# CAN.net
KiCad netlist of a schematic drawn in Altium Designer
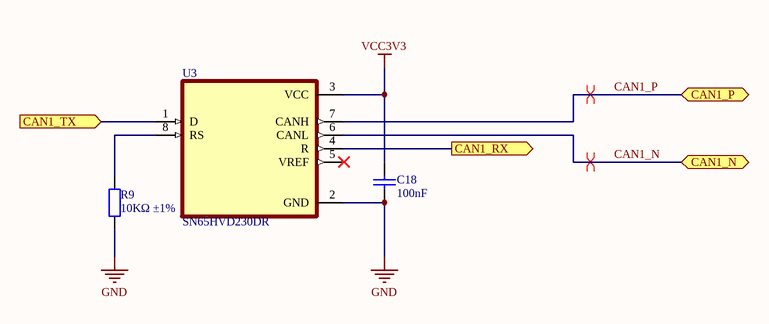
[diagram p0: CAN.SchDoc]

(export (version "E")
  (design (tool "Eeschema 10.0.6"))
  (components
    (comp (ref "C18")
      (value "100nF")
      (footprint "0402_C")
      (description "Chip capacitors")
      (fields
        (field (name "MANUFACTURER") "Samsung Electro-Mechanics")
        (field (name "PARTNUMBER") "CL05B104KO5NNNC")
      )
      (libsource (lib "Cap") (part "0402 100nF (104) 10% 16V"))
    )
    (comp (ref "R9")
      (value "10KΩ ±1%")
      (footprint "0402_R")
      (description "Chip resistor")
      (fields (field (name "MANUFACTURER") "Uniroyal Elec") (field (name "PARTNUMBER") "0402WGF1002TCE"))
      (libsource (lib "RES") (part "0402 10K (1002) 1%"))
    )
    (comp (ref "U3")
      (value "SN65HVD230DR")
      (footprint "SOIC127P599X175-8N")
      (description "3.3 V CAN Transceiver with Standby Mode")
      (fields (field (name "MF") "Texas Instruments"))
      (libsource (lib "SN65HVD230DR") (part "SN65HVD230DR"))
    )
  )
  (nets
    (net (code "1") (name "/CAN1_N") (class "Default")
      (node (ref "U3") (pin "6") (pinfunction "CANL_6") (pintype "output"))
    )
    (net (code "2") (name "/CAN1_P") (class "Default")
      (node (ref "U3") (pin "7") (pinfunction "CANH_7") (pintype "output"))
    )
    (net (code "3") (name "/CAN1_RX") (class "Default")
      (node (ref "U3") (pin "4") (pinfunction "R_4") (pintype "output"))
    )
    (net (code "4") (name "/CAN1_TX") (class "Default")
      (node (ref "U3") (pin "1") (pinfunction "D_1") (pintype "input"))
    )
    (net (code "5") (name "GND") (class "Default")
      (node (ref "C18") (pin "2") (pinfunction "2_2") (pintype "passive"))
      (node (ref "R9") (pin "1") (pinfunction "1_1") (pintype "passive"))
      (node (ref "U3") (pin "2") (pinfunction "GND_2") (pintype "power_in"))
    )
    (net (code "6") (name "Net-(U3-RS)") (class "Default")
      (node (ref "R9") (pin "2") (pinfunction "2_2") (pintype "passive"))
      (node (ref "U3") (pin "8") (pinfunction "RS_8") (pintype "input"))
    )
    (net (code "7") (name "VCC3V3") (class "Default")
      (node (ref "C18") (pin "1") (pinfunction "1_1") (pintype "passive"))
      (node (ref "U3") (pin "3") (pinfunction "VCC_3") (pintype "power_in"))
    )
    (net (code "8") (name "unconnected-(U3-VREF-Pad5)") (class "Default")
      (node (ref "U3") (pin "5") (pinfunction "VREF_5") (pintype "output+no_connect"))
    )
  )
)
